# busy_cube.net
KiCad netlist of a schematic drawn in EAGLE
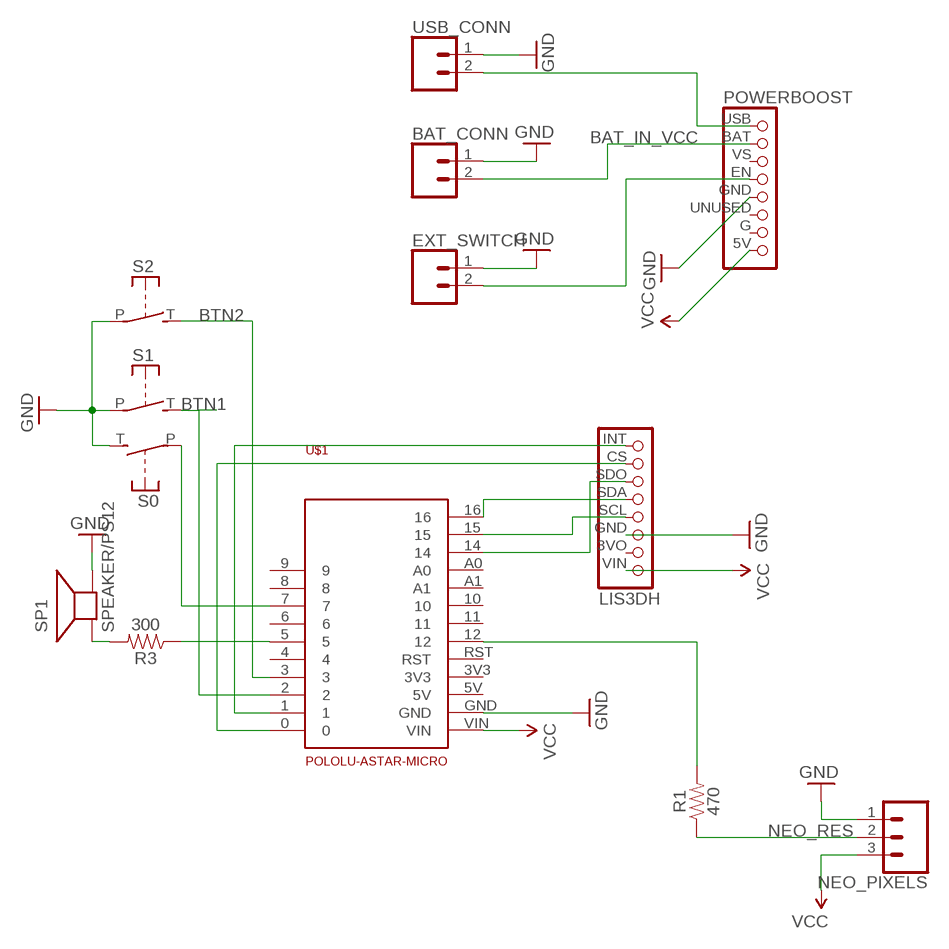
[diagram p0: schematic, sheet 1]

(export (version "E")
  (design (tool "Eeschema 10.0.6"))
  (components
    (comp (ref "BAT_CONN")
      (value "CONN_02-JST-2MM-SMT")
      (footprint "eagle-import:JST-2-SMD")
      (libsource (lib "eagle-import") (part "CONN_02-JST-2MM-SMT"))
    )
    (comp (ref "EXT_SWITCH")
      (value "CONN_02-JST-2MM-SMT")
      (footprint "eagle-import:JST-2-SMD")
      (libsource (lib "eagle-import") (part "CONN_02-JST-2MM-SMT"))
    )
    (comp (ref "LIS3DH")
      (value "ADA-LIS3DHPADS_ONLY")
      (footprint "eagle-import:LIS3DH-1X08")
      (libsource (lib "eagle-import") (part "ADA-LIS3DHPADS_ONLY"))
    )
    (comp (ref "NEO_PIXELS")
      (value "CONN_03LONGPADS")
      (footprint "eagle-import:1X03_LONGPADS")
      (libsource (lib "eagle-import") (part "CONN_03LONGPADS"))
    )
    (comp (ref "POWERBOOST")
      (value "ADA-POWERBOOST-1000CPADS-ONLY")
      (footprint "eagle-import:POWERBOOST-1X08")
      (libsource (lib "eagle-import") (part "ADA-POWERBOOST-1000CPADS-ONLY"))
    )
    (comp (ref "R1")
      (value "470")
      (footprint "eagle-import:AXIAL-0.3")
      (libsource (lib "eagle-import") (part "RESISTORAXIAL-0.3"))
    )
    (comp (ref "R3")
      (value "300")
      (footprint "eagle-import:AXIAL-0.3")
      (libsource (lib "eagle-import") (part "RESISTORAXIAL-0.3"))
    )
    (comp (ref "S0")
      (value "ADA-ARCADE-BTN30MM")
      (footprint "eagle-import:ARCADE-BTN-30MM")
      (libsource (lib "eagle-import") (part "ADA-ARCADE-BTN30MM"))
    )
    (comp (ref "S1")
      (value "ADA-ARCADE-BTN30MM")
      (footprint "eagle-import:ARCADE-BTN-30MM")
      (libsource (lib "eagle-import") (part "ADA-ARCADE-BTN30MM"))
    )
    (comp (ref "S2")
      (value "ADA-ARCADE-BTN30MM")
      (footprint "eagle-import:ARCADE-BTN-30MM")
      (libsource (lib "eagle-import") (part "ADA-ARCADE-BTN30MM"))
    )
    (comp (ref "SP1")
      (value "SPEAKER/PS12")
      (footprint "eagle-import:PS12")
      (libsource (lib "eagle-import") (part "SPEAKER/PS12"))
    )
    (comp (ref "U$1")
      (value "POLOLU-ASTAR-MICRO")
      (footprint "eagle-import:POLOLU-ASTAR-MICRO")
      (libsource (lib "eagle-import") (part "POLOLU-ASTAR-MICRO"))
    )
    (comp (ref "USB_CONN")
      (value "CONN_02-JST-2MM-SMT")
      (footprint "eagle-import:JST-2-SMD")
      (libsource (lib "eagle-import") (part "CONN_02-JST-2MM-SMT"))
    )
  )
  (nets
    (net (code "1") (name "/3V3") (class "Default")
      (node (ref "U$1") (pin "3V3") (pinfunction "3V3_3V3") (pintype "power_in"))
    )
    (net (code "2") (name "/5V") (class "Default")
      (node (ref "U$1") (pin "5V") (pinfunction "5V_5V") (pintype "power_in"))
    )
    (net (code "3") (name "/BAT_IN_VCC") (class "Default")
      (node (ref "BAT_CONN") (pin "2") (pinfunction "1_2") (pintype "passive"))
      (node (ref "POWERBOOST") (pin "BAT") (pinfunction "3VO_BAT") (pintype "passive"))
    )
    (net (code "4") (name "/BTN1") (class "Default")
      (node (ref "S1") (pin "T") (pinfunction "S_T") (pintype "passive"))
      (node (ref "U$1") (pin "2") (pinfunction "2_2") (pintype "bidirectional"))
    )
    (net (code "5") (name "/BTN2") (class "Default")
      (node (ref "S2") (pin "T") (pinfunction "S_T") (pintype "passive"))
      (node (ref "U$1") (pin "3") (pinfunction "3_3") (pintype "bidirectional"))
    )
    (net (code "6") (name "/NEO_RES") (class "Default")
      (node (ref "NEO_PIXELS") (pin "2") (pinfunction "2_2") (pintype "passive"))
      (node (ref "R1") (pin "P$1") (pinfunction "1_P$1") (pintype "passive"))
    )
    (net (code "7") (name "GND") (class "Default")
      (node (ref "BAT_CONN") (pin "1") (pinfunction "2_1") (pintype "passive"))
      (node (ref "EXT_SWITCH") (pin "1") (pinfunction "2_1") (pintype "passive"))
      (node (ref "LIS3DH") (pin "GND") (pinfunction "GND_GND") (pintype "passive"))
      (node (ref "NEO_PIXELS") (pin "1") (pinfunction "1_1") (pintype "passive"))
      (node (ref "POWERBOOST") (pin "GND") (pinfunction "SDA_GND") (pintype "passive"))
      (node (ref "S0") (pin "T") (pinfunction "S_T") (pintype "passive"))
      (node (ref "S1") (pin "P") (pinfunction "P_P") (pintype "passive"))
      (node (ref "S2") (pin "P") (pinfunction "P_P") (pintype "passive"))
      (node (ref "SP1") (pin "P$2") (pinfunction "-_P$2") (pintype "passive"))
      (node (ref "U$1") (pin "GND") (pinfunction "GND_GND") (pintype "power_in"))
      (node (ref "USB_CONN") (pin "1") (pinfunction "2_1") (pintype "passive"))
    )
    (net (code "8") (name "Net-(EXT_SWITCH-1)") (class "Default")
      (node (ref "EXT_SWITCH") (pin "2") (pinfunction "1_2") (pintype "passive"))
      (node (ref "POWERBOOST") (pin "EN") (pinfunction "SCL_EN") (pintype "passive"))
    )
    (net (code "9") (name "Net-(LIS3DH-PadCS)") (class "Default")
      (node (ref "LIS3DH") (pin "CS") (pinfunction "CS_CS") (pintype "passive"))
      (node (ref "U$1") (pin "0") (pinfunction "0_0") (pintype "bidirectional"))
    )
    (net (code "10") (name "Net-(LIS3DH-PadINT)") (class "Default")
      (node (ref "LIS3DH") (pin "INT") (pinfunction "INT_INT") (pintype "passive"))
      (node (ref "U$1") (pin "1") (pinfunction "1_1") (pintype "bidirectional"))
    )
    (net (code "11") (name "Net-(LIS3DH-PadSCL)") (class "Default")
      (node (ref "LIS3DH") (pin "SCL") (pinfunction "SCL_SCL") (pintype "passive"))
      (node (ref "U$1") (pin "15") (pinfunction "15_15") (pintype "bidirectional"))
    )
    (net (code "12") (name "Net-(LIS3DH-PadSDA)") (class "Default")
      (node (ref "LIS3DH") (pin "SDA") (pinfunction "SDA_SDA") (pintype "passive"))
      (node (ref "U$1") (pin "16") (pinfunction "16_16") (pintype "bidirectional"))
    )
    (net (code "13") (name "Net-(LIS3DH-PadSDO)") (class "Default")
      (node (ref "LIS3DH") (pin "SDO") (pinfunction "SDO_SDO") (pintype "passive"))
      (node (ref "U$1") (pin "14") (pinfunction "14_14") (pintype "bidirectional"))
    )
    (net (code "14") (name "Net-(POWERBOOST-VIN)") (class "Default")
      (node (ref "POWERBOOST") (pin "USB") (pinfunction "VIN_USB") (pintype "passive"))
      (node (ref "USB_CONN") (pin "2") (pinfunction "1_2") (pintype "passive"))
    )
    (net (code "15") (name "Net-(R1-2)") (class "Default")
      (node (ref "R1") (pin "P$2") (pinfunction "2_P$2") (pintype "passive"))
      (node (ref "U$1") (pin "12") (pinfunction "12_12") (pintype "bidirectional"))
    )
    (net (code "16") (name "Net-(R3-1)") (class "Default")
      (node (ref "R3") (pin "P$1") (pinfunction "1_P$1") (pintype "passive"))
      (node (ref "U$1") (pin "5") (pinfunction "5_5") (pintype "bidirectional"))
    )
    (net (code "17") (name "Net-(R3-2)") (class "Default")
      (node (ref "R3") (pin "P$2") (pinfunction "2_P$2") (pintype "passive"))
      (node (ref "SP1") (pin "P$1") (pinfunction "+_P$1") (pintype "passive"))
    )
    (net (code "18") (name "Net-(S0-PadP)") (class "Default")
      (node (ref "S0") (pin "P") (pinfunction "P_P") (pintype "passive"))
      (node (ref "U$1") (pin "7") (pinfunction "7_7") (pintype "bidirectional"))
    )
    (net (code "19") (name "VCC") (class "Default")
      (node (ref "LIS3DH") (pin "VIN") (pinfunction "VIN_VIN") (pintype "passive"))
      (node (ref "NEO_PIXELS") (pin "3") (pinfunction "3_3") (pintype "passive"))
      (node (ref "POWERBOOST") (pin "5V") (pinfunction "INT_5V") (pintype "passive"))
      (node (ref "U$1") (pin "VIN") (pinfunction "VIN_VIN") (pintype "power_in"))
    )
    (net (code "20") (name "unconnected-(LIS3DH-Pad3VO)") (class "Default")
      (node (ref "LIS3DH") (pin "3VO") (pinfunction "3VO_3VO") (pintype "passive"))
    )
    (net (code "21") (name "unconnected-(POWERBOOST-CS-PadG)") (class "Default")
      (node (ref "POWERBOOST") (pin "G") (pinfunction "CS_G") (pintype "passive"))
    )
    (net (code "22") (name "unconnected-(POWERBOOST-GND-PadVS)") (class "Default")
      (node (ref "POWERBOOST") (pin "VS") (pinfunction "GND_VS") (pintype "passive"))
    )
    (net (code "23") (name "unconnected-(POWERBOOST-SDO-PadUNUSED)") (class "Default")
      (node (ref "POWERBOOST") (pin "UNUSED") (pinfunction "SDO_UNUSED") (pintype "passive"))
    )
    (net (code "24") (name "unconnected-(U$1-Pad4)") (class "Default")
      (node (ref "U$1") (pin "4") (pinfunction "4_4") (pintype "bidirectional"))
    )
    (net (code "25") (name "unconnected-(U$1-Pad6)") (class "Default")
      (node (ref "U$1") (pin "6") (pinfunction "6_6") (pintype "bidirectional"))
    )
    (net (code "26") (name "unconnected-(U$1-Pad8)") (class "Default")
      (node (ref "U$1") (pin "8") (pinfunction "8_8") (pintype "bidirectional"))
    )
    (net (code "27") (name "unconnected-(U$1-Pad9)") (class "Default")
      (node (ref "U$1") (pin "9") (pinfunction "9_9") (pintype "bidirectional"))
    )
    (net (code "28") (name "unconnected-(U$1-Pad10)") (class "Default")
      (node (ref "U$1") (pin "10") (pinfunction "10_10") (pintype "bidirectional"))
    )
    (net (code "29") (name "unconnected-(U$1-Pad11)") (class "Default")
      (node (ref "U$1") (pin "11") (pinfunction "11_11") (pintype "bidirectional"))
    )
    (net (code "30") (name "unconnected-(U$1-PadA0)") (class "Default")
      (node (ref "U$1") (pin "A0") (pinfunction "A0_A0") (pintype "bidirectional"))
    )
    (net (code "31") (name "unconnected-(U$1-PadA1)") (class "Default")
      (node (ref "U$1") (pin "A1") (pinfunction "A1_A1") (pintype "bidirectional"))
    )
    (net (code "32") (name "unconnected-(U$1-PadRST)") (class "Default")
      (node (ref "U$1") (pin "RST") (pinfunction "RST_RST") (pintype "input"))
    )
  )
)
